# ode_qt_ex.net
KiCad netlist of a schematic drawn in EAGLE
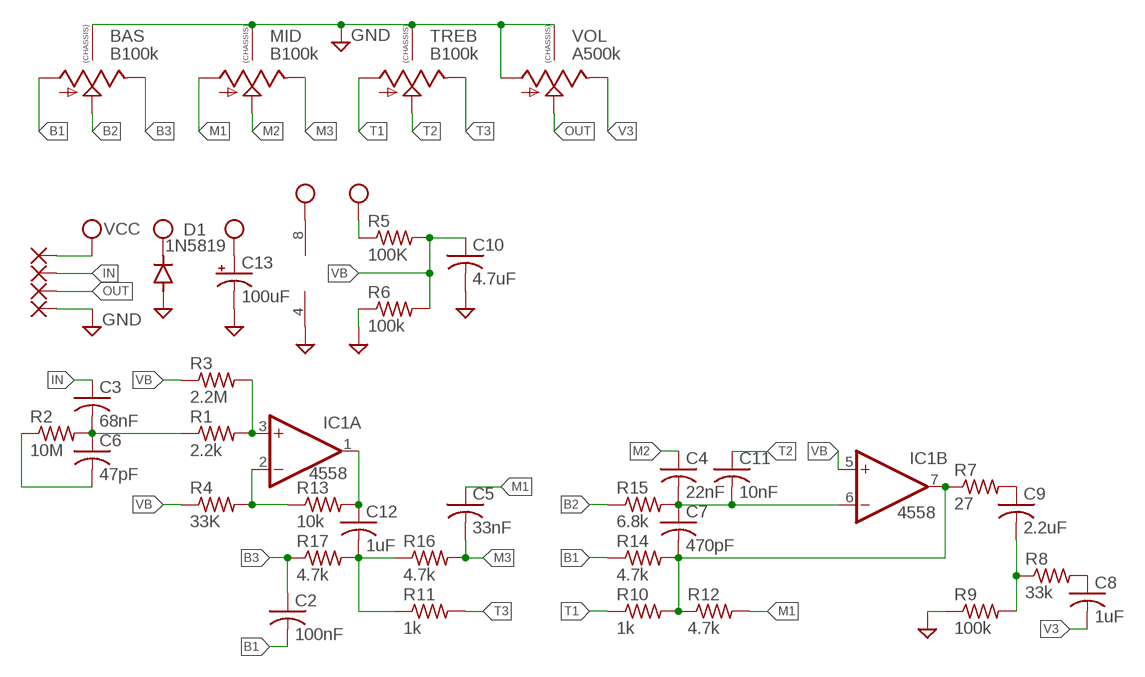
[diagram p0: schematic, sheet 1]

(export (version "E")
  (design (tool "Eeschema 10.0.6"))
  (components
    (comp (ref "BAS")
      (value "B100k")
      (footprint "eagle-import:9MM_SNAP-IN_POT")
      (libsource (lib "eagle-import") (part "9MM_SNAP-IN_POT_CHASSIS"))
    )
    (comp (ref "C2")
      (value "100nF")
      (footprint "eagle-import:C0603")
      (libsource (lib "eagle-import") (part "adafruit_420_C-USC0603"))
    )
    (comp (ref "C3")
      (value "68nF")
      (footprint "eagle-import:C0603")
      (libsource (lib "eagle-import") (part "adafruit_420_C-USC0603"))
    )
    (comp (ref "C4")
      (value "22nF")
      (footprint "eagle-import:C0603")
      (libsource (lib "eagle-import") (part "adafruit_420_C-USC0603"))
    )
    (comp (ref "C5")
      (value "33nF")
      (footprint "eagle-import:C0603")
      (libsource (lib "eagle-import") (part "adafruit_420_C-USC0603"))
    )
    (comp (ref "C6")
      (value "47pF")
      (footprint "eagle-import:C0603")
      (libsource (lib "eagle-import") (part "adafruit_420_C-USC0603"))
    )
    (comp (ref "C7")
      (value "470pF")
      (footprint "eagle-import:C0603")
      (libsource (lib "eagle-import") (part "adafruit_420_C-USC0603"))
    )
    (comp (ref "C8")
      (value "1uF")
      (footprint "eagle-import:C0603")
      (libsource (lib "eagle-import") (part "adafruit_420_C-USC0603"))
    )
    (comp (ref "C9")
      (value "2.2uF")
      (footprint "eagle-import:C0805")
      (libsource (lib "eagle-import") (part "C-USC0805"))
    )
    (comp (ref "C10")
      (value "4.7uF")
      (footprint "eagle-import:C0805")
      (libsource (lib "eagle-import") (part "C-USC0805"))
    )
    (comp (ref "C11")
      (value "10nF")
      (footprint "eagle-import:C0603")
      (libsource (lib "eagle-import") (part "adafruit_420_C-USC0603"))
    )
    (comp (ref "C12")
      (value "1uF")
      (footprint "eagle-import:C0603")
      (libsource (lib "eagle-import") (part "adafruit_420_C-USC0603"))
    )
    (comp (ref "C13")
      (value "100uF")
      (footprint "eagle-import:CPOL-RADIAL-2.5MM-6.5MM")
      (libsource (lib "eagle-import") (part "100UF-POLAR-RADIAL-2.5MM-25V-20%"))
    )
    (comp (ref "D1")
      (value "1N5819")
      (footprint "eagle-import:SOD123")
      (libsource (lib "eagle-import") (part "DIODE-SOD123"))
    )
    (comp (ref "IC1")
      (value "4558")
      (footprint "eagle-import:SO08")
      (libsource (lib "eagle-import") (part "4558DLM"))
    )
    (comp (ref "MID")
      (value "B100k")
      (footprint "eagle-import:9MM_SNAP-IN_POT")
      (libsource (lib "eagle-import") (part "9MM_SNAP-IN_POT_CHASSIS"))
    )
    (comp (ref "PAD1")
      (value "1,6/0,8")
      (footprint "eagle-import:1,6_0,8")
      (libsource (lib "eagle-import") (part "1,6/0,8"))
    )
    (comp (ref "PAD2")
      (value "1,6/0,8")
      (footprint "eagle-import:1,6_0,8")
      (libsource (lib "eagle-import") (part "1,6/0,8"))
    )
    (comp (ref "PAD3")
      (value "1,6/0,8")
      (footprint "eagle-import:1,6_0,8")
      (libsource (lib "eagle-import") (part "1,6/0,8"))
    )
    (comp (ref "PAD4")
      (value "1,6/0,8")
      (footprint "eagle-import:1,6_0,8")
      (libsource (lib "eagle-import") (part "1,6/0,8"))
    )
    (comp (ref "R1")
      (value "2.2k")
      (footprint "eagle-import:R0603")
      (libsource (lib "eagle-import") (part "R-US_R0603"))
    )
    (comp (ref "R2")
      (value "10M")
      (footprint "eagle-import:R0603")
      (libsource (lib "eagle-import") (part "R-US_R0603"))
    )
    (comp (ref "R3")
      (value "2.2M")
      (footprint "eagle-import:R0603")
      (libsource (lib "eagle-import") (part "R-US_R0603"))
    )
    (comp (ref "R4")
      (value "33K")
      (footprint "eagle-import:R0603")
      (libsource (lib "eagle-import") (part "R-US_R0603"))
    )
    (comp (ref "R5")
      (value "100K")
      (footprint "eagle-import:R0603")
      (libsource (lib "eagle-import") (part "R-US_R0603"))
    )
    (comp (ref "R6")
      (value "100k")
      (footprint "eagle-import:R0603")
      (libsource (lib "eagle-import") (part "R-US_R0603"))
    )
    (comp (ref "R7")
      (value "27")
      (footprint "eagle-import:R0603")
      (libsource (lib "eagle-import") (part "R-US_R0603"))
    )
    (comp (ref "R8")
      (value "33k")
      (footprint "eagle-import:R0603")
      (libsource (lib "eagle-import") (part "R-US_R0603"))
    )
    (comp (ref "R9")
      (value "100k")
      (footprint "eagle-import:R0603")
      (libsource (lib "eagle-import") (part "R-US_R0603"))
    )
    (comp (ref "R10")
      (value "1k")
      (footprint "eagle-import:R0603")
      (libsource (lib "eagle-import") (part "R-US_R0603"))
    )
    (comp (ref "R11")
      (value "1k")
      (footprint "eagle-import:R0603")
      (libsource (lib "eagle-import") (part "R-US_R0603"))
    )
    (comp (ref "R12")
      (value "4.7k")
      (footprint "eagle-import:R0603")
      (libsource (lib "eagle-import") (part "R-US_R0603"))
    )
    (comp (ref "R13")
      (value "10k")
      (footprint "eagle-import:R0603")
      (libsource (lib "eagle-import") (part "R-US_R0603"))
    )
    (comp (ref "R14")
      (value "4.7k")
      (footprint "eagle-import:R0603")
      (libsource (lib "eagle-import") (part "R-US_R0603"))
    )
    (comp (ref "R15")
      (value "6.8k")
      (footprint "eagle-import:R0603")
      (libsource (lib "eagle-import") (part "R-US_R0603"))
    )
    (comp (ref "R16")
      (value "4.7k")
      (footprint "eagle-import:R0603")
      (libsource (lib "eagle-import") (part "R-US_R0603"))
    )
    (comp (ref "R17")
      (value "4.7k")
      (footprint "eagle-import:R0603")
      (libsource (lib "eagle-import") (part "R-US_R0603"))
    )
    (comp (ref "TREB")
      (value "B100k")
      (footprint "eagle-import:9MM_SNAP-IN_POT")
      (libsource (lib "eagle-import") (part "9MM_SNAP-IN_POT_CHASSIS"))
    )
    (comp (ref "VOL")
      (value "A500k")
      (footprint "eagle-import:9MM_SNAP-IN_POT")
      (libsource (lib "eagle-import") (part "9MM_SNAP-IN_POT_CHASSIS"))
    )
  )
  (nets
    (net (code "1") (name "B1") (class "Default")
      (node (ref "BAS") (pin "1") (pinfunction "A_1") (pintype "passive"))
      (node (ref "C2") (pin "2") (pinfunction "2_2") (pintype "passive"))
      (node (ref "R14") (pin "1") (pinfunction "1_1") (pintype "passive"))
    )
    (net (code "2") (name "B2") (class "Default")
      (node (ref "BAS") (pin "2") (pinfunction "S_2") (pintype "passive"))
      (node (ref "R15") (pin "1") (pinfunction "1_1") (pintype "passive"))
    )
    (net (code "3") (name "B3") (class "Default")
      (node (ref "BAS") (pin "3") (pinfunction "E_3") (pintype "passive"))
      (node (ref "C2") (pin "1") (pinfunction "1_1") (pintype "passive"))
      (node (ref "R17") (pin "1") (pinfunction "1_1") (pintype "passive"))
    )
    (net (code "4") (name "GND") (class "Default")
      (node (ref "BAS") (pin "CHASSIS1") (pinfunction "P$1_CHASSIS1") (pintype "passive"))
      (node (ref "BAS") (pin "CHASSIS2") (pinfunction "P$1_CHASSIS2") (pintype "passive"))
      (node (ref "C10") (pin "2") (pinfunction "2_2") (pintype "passive"))
      (node (ref "C13") (pin "2") (pinfunction "-_2") (pintype "passive"))
      (node (ref "D1") (pin "A") (pinfunction "A_A") (pintype "passive"))
      (node (ref "IC1") (pin "4") (pinfunction "V-_4") (pintype "power_in"))
      (node (ref "MID") (pin "CHASSIS1") (pinfunction "P$1_CHASSIS1") (pintype "passive"))
      (node (ref "MID") (pin "CHASSIS2") (pinfunction "P$1_CHASSIS2") (pintype "passive"))
      (node (ref "PAD4") (pin "1") (pinfunction "P_1") (pintype "passive"))
      (node (ref "R6") (pin "1") (pinfunction "1_1") (pintype "passive"))
      (node (ref "R9") (pin "1") (pinfunction "1_1") (pintype "passive"))
      (node (ref "TREB") (pin "CHASSIS1") (pinfunction "P$1_CHASSIS1") (pintype "passive"))
      (node (ref "TREB") (pin "CHASSIS2") (pinfunction "P$1_CHASSIS2") (pintype "passive"))
      (node (ref "VOL") (pin "1") (pinfunction "A_1") (pintype "passive"))
      (node (ref "VOL") (pin "CHASSIS1") (pinfunction "P$1_CHASSIS1") (pintype "passive"))
      (node (ref "VOL") (pin "CHASSIS2") (pinfunction "P$1_CHASSIS2") (pintype "passive"))
    )
    (net (code "5") (name "IN") (class "Default")
      (node (ref "C3") (pin "1") (pinfunction "1_1") (pintype "passive"))
      (node (ref "PAD2") (pin "1") (pinfunction "P_1") (pintype "passive"))
    )
    (net (code "6") (name "M1") (class "Default")
      (node (ref "C5") (pin "1") (pinfunction "1_1") (pintype "passive"))
      (node (ref "MID") (pin "1") (pinfunction "A_1") (pintype "passive"))
      (node (ref "R12") (pin "2") (pinfunction "2_2") (pintype "passive"))
    )
    (net (code "7") (name "M2") (class "Default")
      (node (ref "C4") (pin "1") (pinfunction "1_1") (pintype "passive"))
      (node (ref "MID") (pin "2") (pinfunction "S_2") (pintype "passive"))
    )
    (net (code "8") (name "M3") (class "Default")
      (node (ref "C5") (pin "2") (pinfunction "2_2") (pintype "passive"))
      (node (ref "MID") (pin "3") (pinfunction "E_3") (pintype "passive"))
      (node (ref "R16") (pin "2") (pinfunction "2_2") (pintype "passive"))
    )
    (net (code "9") (name "Net-(C3-Pad2)") (class "Default")
      (node (ref "C3") (pin "2") (pinfunction "2_2") (pintype "passive"))
      (node (ref "C6") (pin "1") (pinfunction "1_1") (pintype "passive"))
      (node (ref "R1") (pin "1") (pinfunction "1_1") (pintype "passive"))
      (node (ref "R2") (pin "2") (pinfunction "2_2") (pintype "passive"))
    )
    (net (code "10") (name "Net-(C6-Pad2)") (class "Default")
      (node (ref "C6") (pin "2") (pinfunction "2_2") (pintype "passive"))
      (node (ref "R2") (pin "1") (pinfunction "1_1") (pintype "passive"))
    )
    (net (code "11") (name "Net-(C8-Pad1)") (class "Default")
      (node (ref "C8") (pin "1") (pinfunction "1_1") (pintype "passive"))
      (node (ref "R8") (pin "2") (pinfunction "2_2") (pintype "passive"))
    )
    (net (code "12") (name "Net-(C9-Pad1)") (class "Default")
      (node (ref "C9") (pin "1") (pinfunction "1_1") (pintype "passive"))
      (node (ref "R7") (pin "2") (pinfunction "2_2") (pintype "passive"))
    )
    (net (code "13") (name "Net-(C9-Pad2)") (class "Default")
      (node (ref "C9") (pin "2") (pinfunction "2_2") (pintype "passive"))
      (node (ref "R8") (pin "1") (pinfunction "1_1") (pintype "passive"))
      (node (ref "R9") (pin "2") (pinfunction "2_2") (pintype "passive"))
    )
    (net (code "14") (name "Net-(C12-Pad2)") (class "Default")
      (node (ref "C12") (pin "2") (pinfunction "2_2") (pintype "passive"))
      (node (ref "R11") (pin "1") (pinfunction "1_1") (pintype "passive"))
      (node (ref "R16") (pin "1") (pinfunction "1_1") (pintype "passive"))
      (node (ref "R17") (pin "2") (pinfunction "2_2") (pintype "passive"))
    )
    (net (code "15") (name "Net-(IC1A-+IN)") (class "Default")
      (node (ref "IC1") (pin "3") (pinfunction "+IN_3") (pintype "input"))
      (node (ref "R1") (pin "2") (pinfunction "2_2") (pintype "passive"))
      (node (ref "R3") (pin "2") (pinfunction "2_2") (pintype "passive"))
    )
    (net (code "16") (name "Net-(IC1A--IN)") (class "Default")
      (node (ref "IC1") (pin "2") (pinfunction "-IN_2") (pintype "input"))
      (node (ref "R13") (pin "1") (pinfunction "1_1") (pintype "passive"))
      (node (ref "R4") (pin "2") (pinfunction "2_2") (pintype "passive"))
    )
    (net (code "17") (name "Net-(IC1A-OUT)") (class "Default")
      (node (ref "C12") (pin "1") (pinfunction "1_1") (pintype "passive"))
      (node (ref "IC1") (pin "1") (pinfunction "OUT_1") (pintype "output"))
      (node (ref "R13") (pin "2") (pinfunction "2_2") (pintype "passive"))
    )
    (net (code "18") (name "Net-(IC1B--IN)") (class "Default")
      (node (ref "C11") (pin "2") (pinfunction "2_2") (pintype "passive"))
      (node (ref "C4") (pin "2") (pinfunction "2_2") (pintype "passive"))
      (node (ref "C7") (pin "1") (pinfunction "1_1") (pintype "passive"))
      (node (ref "IC1") (pin "6") (pinfunction "-IN_6") (pintype "input"))
      (node (ref "R15") (pin "2") (pinfunction "2_2") (pintype "passive"))
    )
    (net (code "19") (name "Net-(IC1B-OUT)") (class "Default")
      (node (ref "C7") (pin "2") (pinfunction "2_2") (pintype "passive"))
      (node (ref "IC1") (pin "7") (pinfunction "OUT_7") (pintype "output"))
      (node (ref "R10") (pin "2") (pinfunction "2_2") (pintype "passive"))
      (node (ref "R12") (pin "1") (pinfunction "1_1") (pintype "passive"))
      (node (ref "R14") (pin "2") (pinfunction "2_2") (pintype "passive"))
      (node (ref "R7") (pin "1") (pinfunction "1_1") (pintype "passive"))
    )
    (net (code "20") (name "OUT") (class "Default")
      (node (ref "PAD3") (pin "1") (pinfunction "P_1") (pintype "passive"))
      (node (ref "VOL") (pin "2") (pinfunction "S_2") (pintype "passive"))
    )
    (net (code "21") (name "T1") (class "Default")
      (node (ref "R10") (pin "1") (pinfunction "1_1") (pintype "passive"))
      (node (ref "TREB") (pin "1") (pinfunction "A_1") (pintype "passive"))
    )
    (net (code "22") (name "T2") (class "Default")
      (node (ref "C11") (pin "1") (pinfunction "1_1") (pintype "passive"))
      (node (ref "TREB") (pin "2") (pinfunction "S_2") (pintype "passive"))
    )
    (net (code "23") (name "T3") (class "Default")
      (node (ref "R11") (pin "2") (pinfunction "2_2") (pintype "passive"))
      (node (ref "TREB") (pin "3") (pinfunction "E_3") (pintype "passive"))
    )
    (net (code "24") (name "V3") (class "Default")
      (node (ref "C8") (pin "2") (pinfunction "2_2") (pintype "passive"))
      (node (ref "VOL") (pin "3") (pinfunction "E_3") (pintype "passive"))
    )
    (net (code "25") (name "VB") (class "Default")
      (node (ref "C10") (pin "1") (pinfunction "1_1") (pintype "passive"))
      (node (ref "IC1") (pin "5") (pinfunction "+IN_5") (pintype "input"))
      (node (ref "R3") (pin "1") (pinfunction "1_1") (pintype "passive"))
      (node (ref "R4") (pin "1") (pinfunction "1_1") (pintype "passive"))
      (node (ref "R5") (pin "2") (pinfunction "2_2") (pintype "passive"))
      (node (ref "R6") (pin "2") (pinfunction "2_2") (pintype "passive"))
    )
    (net (code "26") (name "VCC") (class "Default")
      (node (ref "C13") (pin "1") (pinfunction "+_1") (pintype "passive"))
      (node (ref "D1") (pin "C") (pinfunction "C_C") (pintype "passive"))
      (node (ref "IC1") (pin "8") (pinfunction "V+_8") (pintype "power_in"))
      (node (ref "PAD1") (pin "1") (pinfunction "P_1") (pintype "passive"))
      (node (ref "R5") (pin "1") (pinfunction "1_1") (pintype "passive"))
    )
  )
)
